# 1_MCUv3.net
KiCad netlist of a schematic drawn in Altium Designer
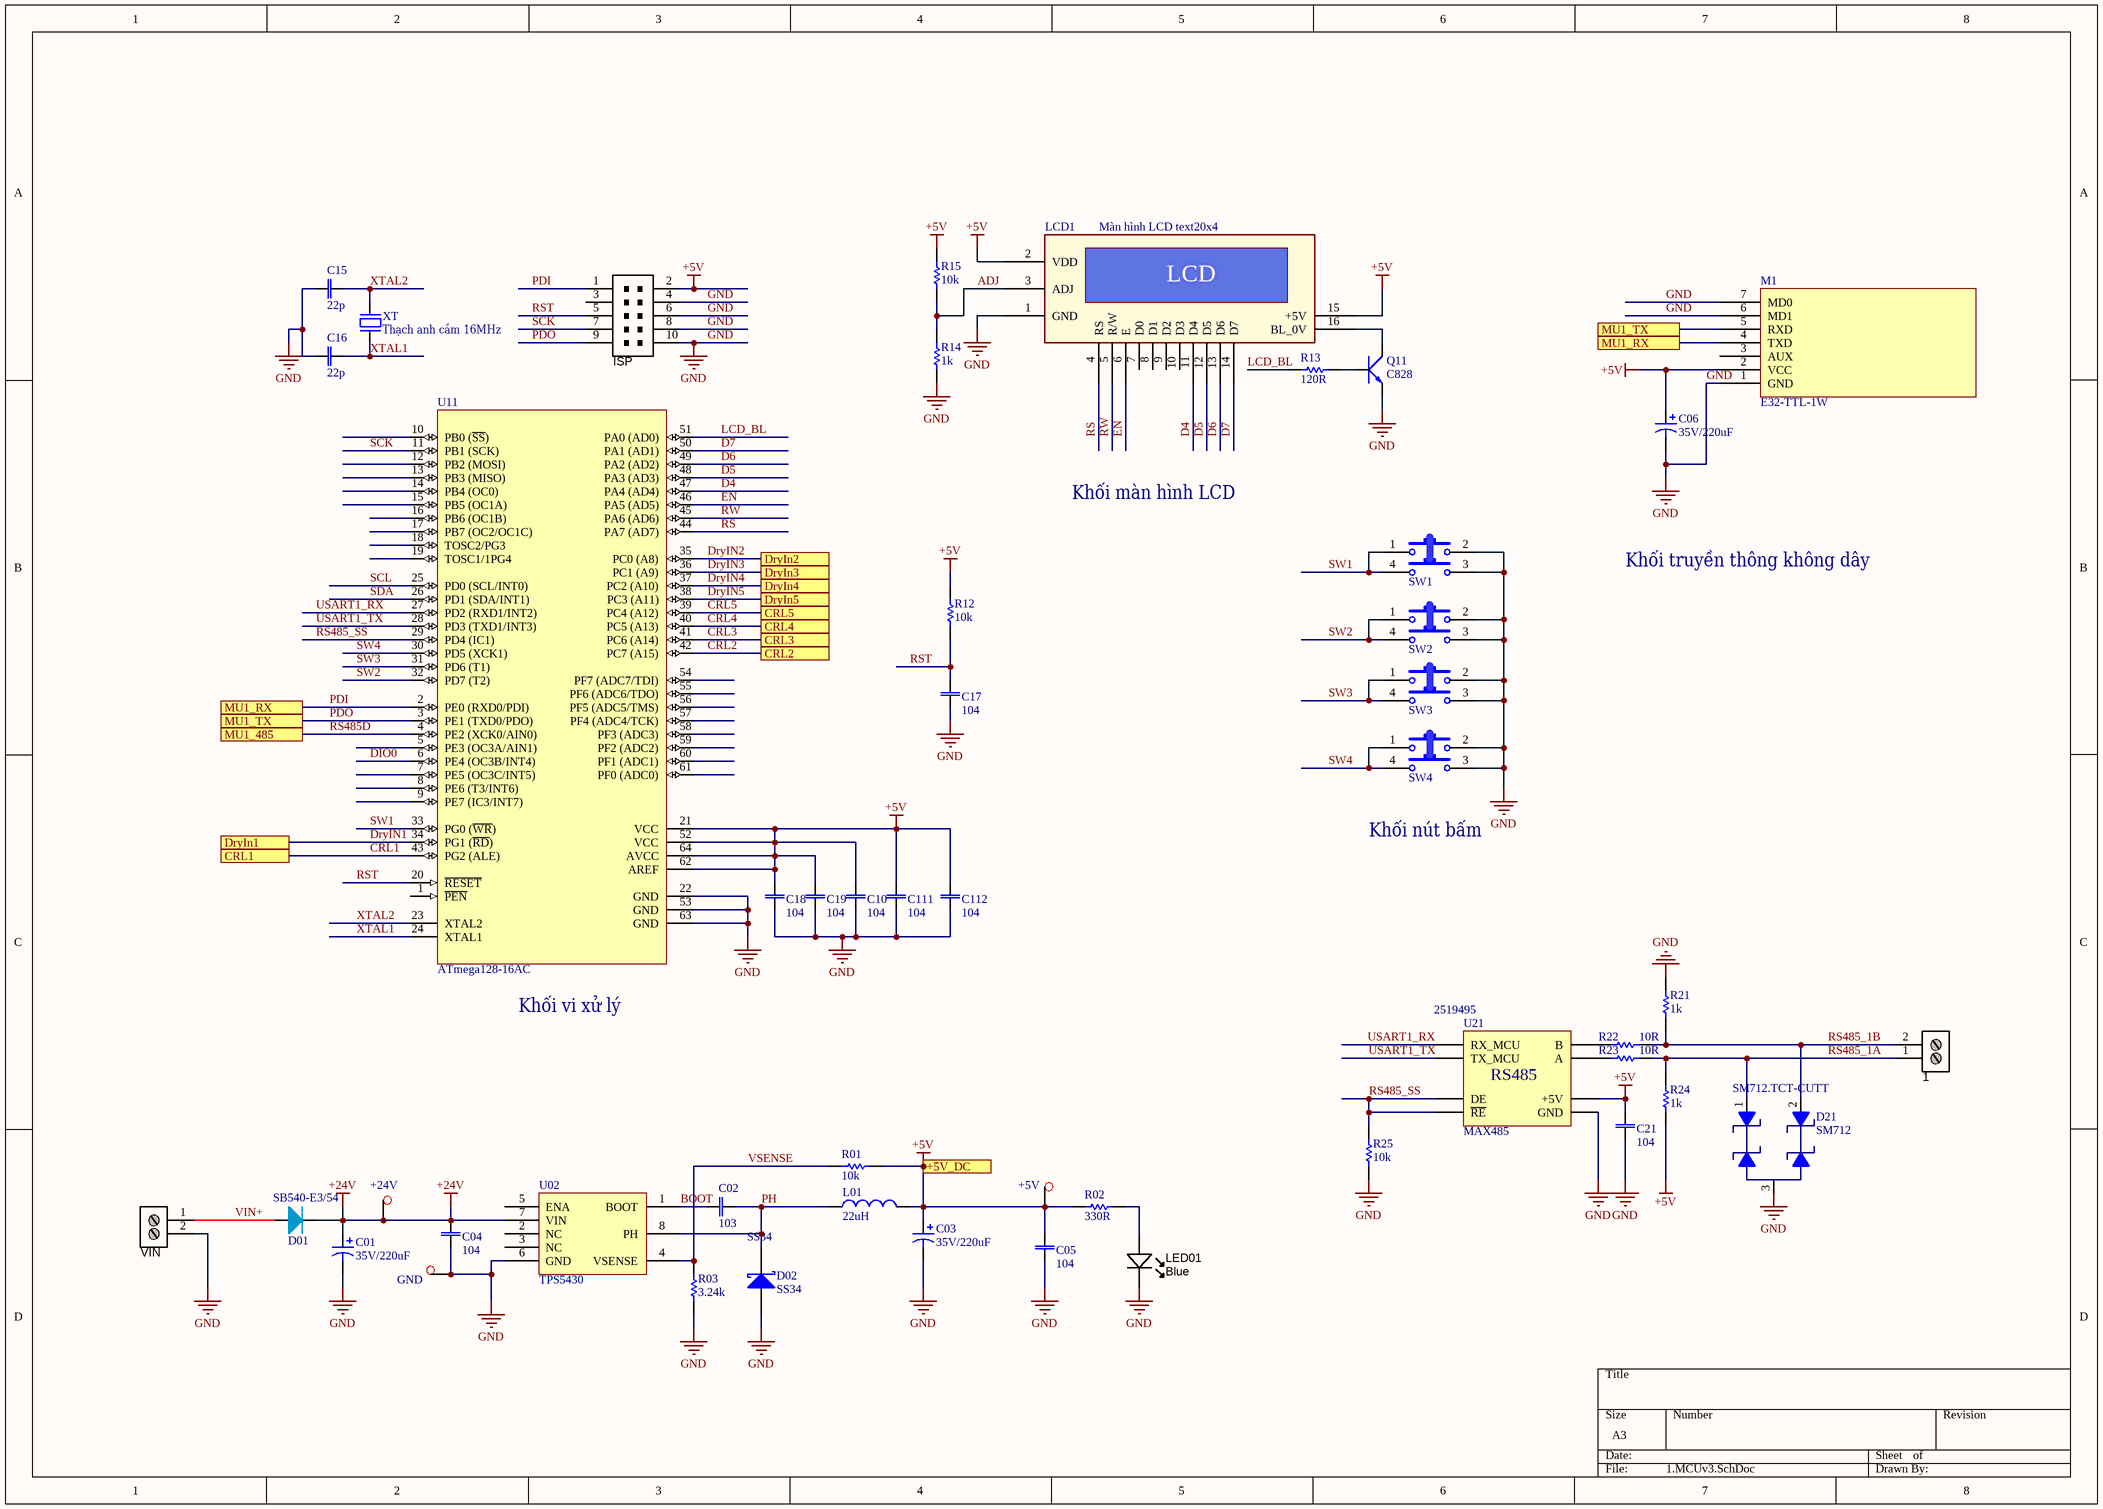
[diagram p0: 1.MCUv3.SchDoc]

(export (version "E")
  (design (tool "Eeschema 10.0.6"))
  (components
    (comp (ref "+5V") (value "TP") (footprint "swatpcblib:TP2") (libsource (lib "swatpcblib") (part "TP")))
    (comp (ref "+24V") (value "TP") (footprint "swatpcblib:TP2") (libsource (lib "swatpcblib") (part "TP")))
    (comp (ref "1")
      (value "Giắc xanh 5.08mm")
      (footprint "2P_PCB1")
      (description "Terminal Block Screw Type THT 2-Position 3.81mm pitch")
      (libsource (lib "PBL - Connectors") (part "2P_ScrewTerm_90S_3.81MM"))
    )
    (comp (ref "C01")
      (value "35V/220uF")
      (footprint "CAPE3.5-5.0MM_Rad_10x14mm")
      (fields (field (name "Comment") "Tụ nhôm cắm35V/220uF"))
      (libsource (lib "Tuan") (part "Cap"))
    )
    (comp (ref "C02")
      (value "103")
      (footprint "swatpcblib:CAP 0805")
      (description "Capacitor non polarized")
      (fields (field (name "Comment") "Tụ điện dán 0805103"))
      (libsource (lib "swatpcblib") (part "CAP NP"))
    )
    (comp (ref "C03")
      (value "35V/220uF")
      (footprint "CAPE3.5-5.0MM_Rad_10x14mm")
      (fields (field (name "Comment") "Tụ nhôm cắm35V/220uF"))
      (libsource (lib "Tuan") (part "Cap"))
    )
    (comp (ref "C04")
      (value "104")
      (footprint "swatpcblib:CAP 0805")
      (description "Capacitor non polarized")
      (fields (field (name "Comment") "Tụ điện dán 0805104"))
      (libsource (lib "swatpcblib") (part "CAP NP"))
    )
    (comp (ref "C05")
      (value "104")
      (footprint "swatpcblib:CAP 0805")
      (description "Capacitor non polarized")
      (fields (field (name "Comment") "Tụ điện dán 0805104"))
      (libsource (lib "swatpcblib") (part "CAP NP"))
    )
    (comp (ref "C06")
      (value "35V/220uF")
      (footprint "CAPE3.5-5.0MM_Rad_10x14mm")
      (fields (field (name "Comment") "Tụ nhôm cắm35V/220uF"))
      (libsource (lib "Tuan") (part "Cap"))
    )
    (comp (ref "C10")
      (value "104")
      (footprint "swatpcblib:CAP 0805")
      (description "Capacitor non polarized")
      (fields (field (name "Comment") "Tụ điện dán 0805104"))
      (libsource (lib "Tuan") (part "CAP NP"))
    )
    (comp (ref "C15")
      (value "22p")
      (footprint "swatpcblib:CAP 0805")
      (description "Capacitor non polarized")
      (fields (field (name "Comment") "Tụ điện dán 080522p"))
      (libsource (lib "Tuan") (part "CAP NP"))
    )
    (comp (ref "C16")
      (value "22p")
      (footprint "swatpcblib:CAP 0805")
      (description "Capacitor non polarized")
      (fields (field (name "Comment") "Tụ điện dán 080522p"))
      (libsource (lib "Tuan") (part "CAP NP"))
    )
    (comp (ref "C17")
      (value "104")
      (footprint "swatpcblib:CAP 0805")
      (description "Capacitor non polarized")
      (fields (field (name "Comment") "Tụ điện dán 0805104"))
      (libsource (lib "Tuan") (part "CAP NP"))
    )
    (comp (ref "C18")
      (value "104")
      (footprint "swatpcblib:CAP 0805")
      (description "Capacitor non polarized")
      (fields (field (name "Comment") "Tụ điện dán 0805104"))
      (libsource (lib "Tuan") (part "CAP NP"))
    )
    (comp (ref "C19")
      (value "104")
      (footprint "swatpcblib:CAP 0805")
      (description "Capacitor non polarized")
      (fields (field (name "Comment") "Tụ điện dán 0805104"))
      (libsource (lib "Tuan") (part "CAP NP"))
    )
    (comp (ref "C21")
      (value "104")
      (footprint "swatpcblib:CAP 0805")
      (description "Capacitor non polarized")
      (fields (field (name "Comment") "Tụ điện dán 0805104"))
      (libsource (lib "Tuan") (part "CAP NP"))
    )
    (comp (ref "C111")
      (value "104")
      (footprint "swatpcblib:CAP 0805")
      (description "Capacitor non polarized")
      (fields (field (name "Comment") "Tụ điện dán 0805104"))
      (libsource (lib "Tuan") (part "CAP NP"))
    )
    (comp (ref "C112")
      (value "104")
      (footprint "swatpcblib:CAP 0805")
      (description "Capacitor non polarized")
      (fields (field (name "Comment") "Tụ điện dán 0805104"))
      (libsource (lib "Tuan") (part "CAP NP"))
    )
    (comp (ref "D01")
      (value "Đi ốt dánchân DO-214AB")
      (footprint "DO-214AA")
      (fields
        (field (name "SUPPLIER PART NUMBER 1") "SB540-E3/54")
        (field (name "MANUFACTURER") "Vishay")
        (field (name "MANUFACTURER PART NUMBER") "SB540-E3/54")
        (field (name "VOLTAGE") "40V")
      )
      (libsource (lib "Tuan") (part "Diode"))
    )
    (comp (ref "D02")
      (value "SS34")
      (footprint "SMD diode")
      (fields
        (field (name "SUPPLIER PART NUMBER 1") "SS34")
        (field (name "MANUFACTURER") "ON Semiconductor / Fairchild")
        (field (name "VOLTAGE") "40V")
      )
      (libsource (lib "Tuan") (part "Diode Schottky"))
    )
    (comp (ref "D21")
      (value "SM712")
      (footprint "SOT23 TOP")
      (fields
        (field (name "SUPPLIER PART NUMBER 1") "SM712.TCT-CUTT")
        (field (name "MANUFACTURER") "Semtech")
        (field (name "MANUFACTURER PART NUMBER") "SM712.TCT")
      )
      (libsource (lib "swatpcblib") (part "Diode SM712"))
    )
    (comp (ref "GND") (value "TP") (footprint "swatpcblib:TP2") (libsource (lib "swatpcblib") (part "TP")))
    (comp (ref "ISP")
      (value "Giắc đôi 5x2 chân 2.54mm")
      (footprint "10P_PCB_HEADER_BRD_MNT")
      (description "Header THD 10 POS Double-row 2.54mm pitch")
      (libsource (lib "PBL - Connectors") (part "CONN_HEADER_2x5P_0.100in_Male"))
    )
    (comp (ref "L01")
      (value "22uH")
      (footprint "Inductor 12x12x6")
      (fields (field (name "Comment") "Cuộn cảm dán22uH"))
      (libsource (lib "swatpcblib") (part "Inductor"))
    )
    (comp (ref "LCD1")
      (value "Màn hình LCD text20x4")
      (footprint "LCD 20x4")
      (description "Text LCD")
      (libsource (lib "Tuan") (part "LCD 16x2"))
    )
    (comp (ref "LED01")
      (value "Blue")
      (footprint "LED-0805-K")
      (description "LED 0805 SMD Blue 100mcd 470nm")
      (fields (field (name "COLOR") "Blue"))
      (libsource (lib "PBL - Light Sources") (part "LED_SMD_Blue_0805_100mcd"))
    )
    (comp (ref "M1")
      (value "E32-TTL-1W")
      (footprint "RF_AS32")
      (description "AS32-TTL-1W")
      (fields (field (name "Comment") "Module thu phát không dây RFE32-TTL-1W"))
      (libsource (lib "DnsSchLib") (part "AS32-TTL-1W"))
    )
    (comp (ref "Q11")
      (value "C828")
      (footprint "SOT23 TOP")
      (description "Transistor C828 C1815....")
      (libsource (lib "Tuan") (part "NPN"))
    )
    (comp (ref "R01")
      (value "10k")
      (footprint "swatpcblib:RES 0805")
      (description "Resistor")
      (fields (field (name "Comment") "Điện trở dán 080510k"))
      (libsource (lib "swatpcblib") (part "Res"))
    )
    (comp (ref "R02")
      (value "330R")
      (footprint "swatpcblib:RES 0805")
      (description "Resistor")
      (fields (field (name "Comment") "Điện trở dán 0805330R"))
      (libsource (lib "swatpcblib") (part "Res"))
    )
    (comp (ref "R03")
      (value "3.24k")
      (footprint "swatpcblib:RES 0805")
      (description "Resistor")
      (fields (field (name "Comment") "Điện trở dán 08053.24k"))
      (libsource (lib "swatpcblib") (part "Res"))
    )
    (comp (ref "R12")
      (value "10k")
      (footprint "swatpcblib:RES 0805")
      (description "Resistor")
      (fields (field (name "Comment") "Điện trở dán 080510k"))
      (libsource (lib "Tuan") (part "Res"))
    )
    (comp (ref "R13")
      (value "120R")
      (footprint "swatpcblib:RES 0805")
      (description "Resistor")
      (fields (field (name "Comment") "Điện trở dán 0805120R"))
      (libsource (lib "Tuan") (part "Res"))
    )
    (comp (ref "R14")
      (value "1k")
      (footprint "swatpcblib:RES 0805")
      (description "Resistor")
      (fields (field (name "Comment") "Điện trở dán 08051k"))
      (libsource (lib "Tuan") (part "Res"))
    )
    (comp (ref "R15")
      (value "10k")
      (footprint "swatpcblib:RES 0805")
      (description "Resistor")
      (fields (field (name "Comment") "Điện trở dán 080510k"))
      (libsource (lib "Tuan") (part "Res"))
    )
    (comp (ref "R21")
      (value "1k")
      (footprint "swatpcblib:RES 0805")
      (description "Resistor")
      (fields (field (name "Comment") "Điện trở dán 08051k"))
      (libsource (lib "Tuan") (part "Res"))
    )
    (comp (ref "R22")
      (value "10R")
      (footprint "swatpcblib:RES 0805")
      (description "Resistor")
      (fields (field (name "Comment") "Điện trở dán 080510R"))
      (libsource (lib "Tuan") (part "Res"))
    )
    (comp (ref "R23")
      (value "10R")
      (footprint "swatpcblib:RES 0805")
      (description "Resistor")
      (fields (field (name "Comment") "Điện trở dán 080510R"))
      (libsource (lib "Tuan") (part "Res"))
    )
    (comp (ref "R24")
      (value "1k")
      (footprint "swatpcblib:RES 0805")
      (description "Resistor")
      (fields (field (name "Comment") "Điện trở dán 08051k"))
      (libsource (lib "Tuan") (part "Res"))
    )
    (comp (ref "R25")
      (value "10k")
      (footprint "swatpcblib:RES 0805")
      (description "Resistor")
      (fields (field (name "Comment") "Điện trở dán 080510k"))
      (libsource (lib "Tuan") (part "Res"))
    )
    (comp (ref "SW1")
      (value "Nút bấm 4 chân cắm12x12x6mm")
      (footprint "hayqua:SW 12x12x4")
      (libsource (lib "Tuan") (part "SW-4P-Small"))
    )
    (comp (ref "SW2")
      (value "Nút bấm 4 chân cắm12x12x6mm")
      (footprint "hayqua:SW 12x12x4")
      (libsource (lib "Tuan") (part "SW-4P-Small"))
    )
    (comp (ref "SW3")
      (value "Nút bấm 4 chân cắm12x12x6mm")
      (footprint "hayqua:SW 12x12x4")
      (libsource (lib "Tuan") (part "SW-4P-Small"))
    )
    (comp (ref "SW4")
      (value "Nút bấm 4 chân cắm12x12x6mm")
      (footprint "hayqua:SW 12x12x4")
      (libsource (lib "Tuan") (part "SW-4P-Small"))
    )
    (comp (ref "U02") (value "TPS5430") (footprint "SOIC 8") (libsource (lib "Tuan") (part "TPS5430")))
    (comp (ref "U11")
      (value "ATmega128-16AC")
      (footprint "64A_N")
      (description "8-Bit AVR Microcontroller with 128K Bytes of In-System Programmable Flash Memory")
      (fields (field (name "PUBLISHER") "Altium Limited"))
      (libsource (lib "Atmel Microcontroller 8-Bit AVR") (part "ATmega128-16AC"))
    )
    (comp (ref "U21")
      (value "MAX4858 chân cắm")
      (footprint "SOIC 8")
      (description "RS485")
      (fields
        (field (name "VL2") "MAX485")
        (field (name "SUPPLIER PART NUMBER 1") "2519495")
        (field (name "MANUFACTURER") "Maxim")
        (field (name "MANUFACTURER PART NUMBER") "MAX485CSA+")
      )
      (libsource (lib "swatpcblib") (part "485"))
    )
    (comp (ref "VIN")
      (value "Giắc xanh 5.08mm")
      (footprint "2P_PCB1")
      (description "Terminal Block Screw Type THT 2-Position 3.81mm pitch")
      (libsource (lib "") (part "2P_ScrewTerm_90S_3.81MM_1"))
    )
    (comp (ref "XT")
      (value "Thạch anh cắm 16MHz")
      (footprint "XT2")
      (libsource (lib "Tuan") (part "Crystal"))
    )
  )
  (nets
    (net (code "1") (name "+5V") (class "Default")
      (node (ref "+5V") (pin "1") (pinfunction "1_1") (pintype "passive"))
      (node (ref "C03") (pin "1") (pinfunction "1_1") (pintype "passive"))
      (node (ref "C05") (pin "2") (pinfunction "2_2") (pintype "passive"))
      (node (ref "C06") (pin "1") (pinfunction "1_1") (pintype "passive"))
      (node (ref "C10") (pin "2") (pinfunction "2_2") (pintype "passive"))
      (node (ref "C111") (pin "2") (pinfunction "2_2") (pintype "passive"))
      (node (ref "C112") (pin "2") (pinfunction "2_2") (pintype "passive"))
      (node (ref "C18") (pin "2") (pinfunction "2_2") (pintype "passive"))
      (node (ref "C19") (pin "2") (pinfunction "2_2") (pintype "passive"))
      (node (ref "C21") (pin "1") (pinfunction "1_1") (pintype "passive"))
      (node (ref "ISP") (pin "2") (pinfunction "2_2") (pintype "passive"))
      (node (ref "L01") (pin "2") (pinfunction "2_2") (pintype "passive"))
      (node (ref "LCD1") (pin "15") (pinfunction "+5V_15") (pintype "passive"))
      (node (ref "LCD1") (pin "2") (pinfunction "VDD_2") (pintype "passive"))
      (node (ref "M1") (pin "2") (pinfunction "VCC_2") (pintype "passive"))
      (node (ref "R01") (pin "1") (pinfunction "1_1") (pintype "passive"))
      (node (ref "R02") (pin "2") (pinfunction "2_2") (pintype "passive"))
      (node (ref "R12") (pin "2") (pinfunction "2_2") (pintype "passive"))
      (node (ref "R15") (pin "2") (pinfunction "2_2") (pintype "passive"))
      (node (ref "R24") (pin "1") (pinfunction "1_1") (pintype "passive"))
      (node (ref "U11") (pin "21") (pinfunction "VCC_21") (pintype "power_in"))
      (node (ref "U11") (pin "52") (pinfunction "VCC_52") (pintype "power_in"))
      (node (ref "U11") (pin "62") (pinfunction "AREF_62") (pintype "passive"))
      (node (ref "U11") (pin "64") (pinfunction "AVCC_64") (pintype "power_in"))
      (node (ref "U21") (pin "8") (pinfunction "+5V_8") (pintype "passive"))
    )
    (net (code "2") (name "+24V") (class "Default")
      (node (ref "+24V") (pin "1") (pinfunction "1_1") (pintype "passive"))
      (node (ref "C01") (pin "1") (pinfunction "1_1") (pintype "passive"))
      (node (ref "C04") (pin "2") (pinfunction "2_2") (pintype "passive"))
      (node (ref "D01") (pin "2") (pinfunction "K_2") (pintype "passive"))
      (node (ref "U02") (pin "7") (pinfunction "VIN_7") (pintype "power_in"))
    )
    (net (code "3") (name "/ADJ") (class "Default")
      (node (ref "LCD1") (pin "3") (pinfunction "ADJ_3") (pintype "passive"))
      (node (ref "R14") (pin "2") (pinfunction "2_2") (pintype "passive"))
      (node (ref "R15") (pin "1") (pinfunction "1_1") (pintype "passive"))
    )
    (net (code "4") (name "/BOOT") (class "Default")
      (node (ref "C02") (pin "1") (pinfunction "1_1") (pintype "passive"))
      (node (ref "U02") (pin "1") (pinfunction "BOOT_1") (pintype "power_in"))
    )
    (net (code "5") (name "/CRL1") (class "Default")
      (node (ref "U11") (pin "43") (pinfunction "PG2_(ALE)_43") (pintype "bidirectional"))
    )
    (net (code "6") (name "/CRL2") (class "Default")
      (node (ref "U11") (pin "42") (pinfunction "PC7_(A15)_42") (pintype "bidirectional"))
    )
    (net (code "7") (name "/CRL3") (class "Default")
      (node (ref "U11") (pin "41") (pinfunction "PC6_(A14)_41") (pintype "bidirectional"))
    )
    (net (code "8") (name "/CRL4") (class "Default")
      (node (ref "U11") (pin "40") (pinfunction "PC5_(A13)_40") (pintype "bidirectional"))
    )
    (net (code "9") (name "/CRL5") (class "Default")
      (node (ref "U11") (pin "39") (pinfunction "PC4_(A12)_39") (pintype "bidirectional"))
    )
    (net (code "10") (name "/D4") (class "Default")
      (node (ref "LCD1") (pin "11") (pinfunction "D4_11") (pintype "passive"))
      (node (ref "U11") (pin "47") (pinfunction "PA4_(AD4)_47") (pintype "bidirectional"))
    )
    (net (code "11") (name "/D5") (class "Default")
      (node (ref "LCD1") (pin "12") (pinfunction "D5_12") (pintype "passive"))
      (node (ref "U11") (pin "48") (pinfunction "PA3_(AD3)_48") (pintype "bidirectional"))
    )
    (net (code "12") (name "/D6") (class "Default")
      (node (ref "LCD1") (pin "13") (pinfunction "D6_13") (pintype "passive"))
      (node (ref "U11") (pin "49") (pinfunction "PA2_(AD2)_49") (pintype "bidirectional"))
    )
    (net (code "13") (name "/D7") (class "Default")
      (node (ref "LCD1") (pin "14") (pinfunction "D7_14") (pintype "passive"))
      (node (ref "U11") (pin "50") (pinfunction "PA1_(AD1)_50") (pintype "bidirectional"))
    )
    (net (code "14") (name "/DIO0") (class "Default")
      (node (ref "U11") (pin "6") (pinfunction "PE4_(OC3B/INT4)_6") (pintype "bidirectional"))
    )
    (net (code "15") (name "/DryIN1") (class "Default")
      (node (ref "U11") (pin "34") (pinfunction "PG1_(~{RD})_34") (pintype "bidirectional"))
    )
    (net (code "16") (name "/DryIN2") (class "Default")
      (node (ref "U11") (pin "35") (pinfunction "PC0_(A8)_35") (pintype "bidirectional"))
    )
    (net (code "17") (name "/DryIN3") (class "Default")
      (node (ref "U11") (pin "36") (pinfunction "PC1_(A9)_36") (pintype "bidirectional"))
    )
    (net (code "18") (name "/DryIN4") (class "Default")
      (node (ref "U11") (pin "37") (pinfunction "PC2_(A10)_37") (pintype "bidirectional"))
    )
    (net (code "19") (name "/DryIN5") (class "Default")
      (node (ref "U11") (pin "38") (pinfunction "PC3_(A11)_38") (pintype "bidirectional"))
    )
    (net (code "20") (name "/EN") (class "Default")
      (node (ref "LCD1") (pin "6") (pinfunction "E_6") (pintype "passive"))
      (node (ref "U11") (pin "46") (pinfunction "PA5_(AD5)_46") (pintype "bidirectional"))
    )
    (net (code "21") (name "/LCD_BL") (class "Default")
      (node (ref "R13") (pin "2") (pinfunction "2_2") (pintype "passive"))
      (node (ref "U11") (pin "51") (pinfunction "PA0_(AD0)_51") (pintype "bidirectional"))
    )
    (net (code "22") (name "/PDI") (class "Default")
      (node (ref "ISP") (pin "1") (pinfunction "1_1") (pintype "passive"))
      (node (ref "M1") (pin "4") (pinfunction "TXD_4") (pintype "passive"))
      (node (ref "U11") (pin "2") (pinfunction "PE0_(RXD0/PDI)_2") (pintype "bidirectional"))
    )
    (net (code "23") (name "/PDO") (class "Default")
      (node (ref "ISP") (pin "9") (pinfunction "9_9") (pintype "passive"))
      (node (ref "M1") (pin "5") (pinfunction "RXD_5") (pintype "passive"))
      (node (ref "U11") (pin "3") (pinfunction "PE1_(TXD0/PDO)_3") (pintype "bidirectional"))
    )
    (net (code "24") (name "/PH") (class "Default")
      (node (ref "C02") (pin "2") (pinfunction "2_2") (pintype "passive"))
      (node (ref "D02") (pin "2") (pinfunction "K_2") (pintype "passive"))
      (node (ref "L01") (pin "1") (pinfunction "1_1") (pintype "passive"))
      (node (ref "U02") (pin "8") (pinfunction "PH_8") (pintype "power_in"))
    )
    (net (code "25") (name "/RS") (class "Default")
      (node (ref "LCD1") (pin "4") (pinfunction "RS_4") (pintype "passive"))
      (node (ref "U11") (pin "44") (pinfunction "PA7_(AD7)_44") (pintype "bidirectional"))
    )
    (net (code "26") (name "/RS485D") (class "Default")
      (node (ref "U11") (pin "4") (pinfunction "PE2_(XCK0/AIN0)_4") (pintype "bidirectional"))
    )
    (net (code "27") (name "/RS485_1A") (class "Default")
      (node (ref "1") (pin "1") (pinfunction "1_1") (pintype "passive"))
      (node (ref "D21") (pin "1") (pinfunction "IO1_1") (pintype "passive"))
      (node (ref "R23") (pin "2") (pinfunction "2_2") (pintype "passive"))
      (node (ref "R24") (pin "2") (pinfunction "2_2") (pintype "passive"))
    )
    (net (code "28") (name "/RS485_1B") (class "Default")
      (node (ref "1") (pin "2") (pinfunction "2_2") (pintype "passive"))
      (node (ref "D21") (pin "2") (pinfunction "IO2_2") (pintype "passive"))
      (node (ref "R21") (pin "1") (pinfunction "1_1") (pintype "passive"))
      (node (ref "R22") (pin "2") (pinfunction "2_2") (pintype "passive"))
    )
    (net (code "29") (name "/RS485_SS") (class "Default")
      (node (ref "R25") (pin "2") (pinfunction "2_2") (pintype "passive"))
      (node (ref "U11") (pin "29") (pinfunction "PD4_(IC1)_29") (pintype "bidirectional"))
      (node (ref "U21") (pin "2") (pinfunction "~{RE}_2") (pintype "passive"))
      (node (ref "U21") (pin "3") (pinfunction "DE_3") (pintype "passive"))
    )
    (net (code "30") (name "/RST") (class "Default")
      (node (ref "C17") (pin "2") (pinfunction "2_2") (pintype "passive"))
      (node (ref "ISP") (pin "5") (pinfunction "5_5") (pintype "passive"))
      (node (ref "R12") (pin "1") (pinfunction "1_1") (pintype "passive"))
      (node (ref "U11") (pin "20") (pinfunction "~{RESET}_20") (pintype "input"))
    )
    (net (code "31") (name "/RW") (class "Default")
      (node (ref "LCD1") (pin "5") (pinfunction "R/W_5") (pintype "passive"))
      (node (ref "U11") (pin "45") (pinfunction "PA6_(AD6)_45") (pintype "bidirectional"))
    )
    (net (code "32") (name "/SCK") (class "Default")
      (node (ref "ISP") (pin "7") (pinfunction "7_7") (pintype "passive"))
      (node (ref "U11") (pin "11") (pinfunction "PB1_(SCK)_11") (pintype "bidirectional"))
    )
    (net (code "33") (name "/SCL") (class "Default")
      (node (ref "U11") (pin "25") (pinfunction "PD0_(SCL/INT0)_25") (pintype "bidirectional"))
    )
    (net (code "34") (name "/SDA") (class "Default")
      (node (ref "U11") (pin "26") (pinfunction "PD1_(SDA/INT1)_26") (pintype "bidirectional"))
    )
    (net (code "35") (name "/SW1") (class "Default")
      (node (ref "SW1") (pin "1") (pinfunction "1_1") (pintype "passive"))
      (node (ref "SW1") (pin "4") (pinfunction "4_4") (pintype "passive"))
      (node (ref "U11") (pin "33") (pinfunction "PG0_(~{WR})_33") (pintype "bidirectional"))
    )
    (net (code "36") (name "/SW2") (class "Default")
      (node (ref "SW2") (pin "1") (pinfunction "1_1") (pintype "passive"))
      (node (ref "SW2") (pin "4") (pinfunction "4_4") (pintype "passive"))
      (node (ref "U11") (pin "32") (pinfunction "PD7_(T2)_32") (pintype "bidirectional"))
    )
    (net (code "37") (name "/SW3") (class "Default")
      (node (ref "SW3") (pin "1") (pinfunction "1_1") (pintype "passive"))
      (node (ref "SW3") (pin "4") (pinfunction "4_4") (pintype "passive"))
      (node (ref "U11") (pin "31") (pinfunction "PD6_(T1)_31") (pintype "bidirectional"))
    )
    (net (code "38") (name "/SW4") (class "Default")
      (node (ref "SW4") (pin "1") (pinfunction "1_1") (pintype "passive"))
      (node (ref "SW4") (pin "4") (pinfunction "4_4") (pintype "passive"))
      (node (ref "U11") (pin "30") (pinfunction "PD5_(XCK1)_30") (pintype "bidirectional"))
    )
    (net (code "39") (name "/USART1_RX") (class "Default")
      (node (ref "U11") (pin "27") (pinfunction "PD2_(RXD1/INT2)_27") (pintype "bidirectional"))
      (node (ref "U21") (pin "1") (pinfunction "RX_MCU_1") (pintype "passive"))
    )
    (net (code "40") (name "/USART1_TX") (class "Default")
      (node (ref "U11") (pin "28") (pinfunction "PD3_(TXD1/INT3)_28") (pintype "bidirectional"))
      (node (ref "U21") (pin "4") (pinfunction "TX_MCU_4") (pintype "passive"))
    )
    (net (code "41") (name "/VIN+") (class "Default")
      (node (ref "D01") (pin "1") (pinfunction "A_1") (pintype "passive"))
      (node (ref "VIN") (pin "1") (pinfunction "1_1") (pintype "passive"))
    )
    (net (code "42") (name "/VSENSE") (class "Default")
      (node (ref "R01") (pin "2") (pinfunction "2_2") (pintype "passive"))
      (node (ref "R03") (pin "2") (pinfunction "2_2") (pintype "passive"))
      (node (ref "U02") (pin "4") (pinfunction "VSENSE_4") (pintype "power_in"))
    )
    (net (code "43") (name "/XTAL1") (class "Default")
      (node (ref "C16") (pin "1") (pinfunction "1_1") (pintype "passive"))
      (node (ref "U11") (pin "24") (pinfunction "XTAL1_24") (pintype "passive"))
      (node (ref "XT") (pin "1") (pinfunction "1_1") (pintype "passive"))
    )
    (net (code "44") (name "/XTAL2") (class "Default")
      (node (ref "C15") (pin "1") (pinfunction "1_1") (pintype "passive"))
      (node (ref "U11") (pin "23") (pinfunction "XTAL2_23") (pintype "passive"))
      (node (ref "XT") (pin "2") (pinfunction "2_2") (pintype "passive"))
    )
    (net (code "45") (name "GND") (class "Default")
      (node (ref "C01") (pin "2") (pinfunction "2_2") (pintype "passive"))
      (node (ref "C03") (pin "2") (pinfunction "2_2") (pintype "passive"))
      (node (ref "C04") (pin "1") (pinfunction "1_1") (pintype "passive"))
      (node (ref "C05") (pin "1") (pinfunction "1_1") (pintype "passive"))
      (node (ref "C06") (pin "2") (pinfunction "2_2") (pintype "passive"))
      (node (ref "C10") (pin "1") (pinfunction "1_1") (pintype "passive"))
      (node (ref "C111") (pin "1") (pinfunction "1_1") (pintype "passive"))
      (node (ref "C112") (pin "1") (pinfunction "1_1") (pintype "passive"))
      (node (ref "C15") (pin "2") (pinfunction "2_2") (pintype "passive"))
      (node (ref "C16") (pin "2") (pinfunction "2_2") (pintype "passive"))
      (node (ref "C17") (pin "1") (pinfunction "1_1") (pintype "passive"))
      (node (ref "C18") (pin "1") (pinfunction "1_1") (pintype "passive"))
      (node (ref "C19") (pin "1") (pinfunction "1_1") (pintype "passive"))
      (node (ref "C21") (pin "2") (pinfunction "2_2") (pintype "passive"))
      (node (ref "D02") (pin "1") (pinfunction "A_1") (pintype "passive"))
      (node (ref "D21") (pin "3") (pinfunction "GND_3") (pintype "passive"))
      (node (ref "GND") (pin "1") (pinfunction "1_1") (pintype "passive"))
      (node (ref "ISP") (pin "10") (pinfunction "10_10") (pintype "passive"))
      (node (ref "ISP") (pin "4") (pinfunction "4_4") (pintype "passive"))
      (node (ref "ISP") (pin "6") (pinfunction "6_6") (pintype "passive"))
      (node (ref "ISP") (pin "8") (pinfunction "8_8") (pintype "passive"))
      (node (ref "LCD1") (pin "1") (pinfunction "GND_1") (pintype "passive"))
      (node (ref "LED01") (pin "K") (pinfunction "K_K") (pintype "passive"))
      (node (ref "M1") (pin "1") (pinfunction "GND_1") (pintype "passive"))
      (node (ref "M1") (pin "6") (pinfunction "MD1_6") (pintype "passive"))
      (node (ref "M1") (pin "7") (pinfunction "MD0_7") (pintype "passive"))
      (node (ref "Q11") (pin "3") (pinfunction "E_3") (pintype "passive"))
      (node (ref "R03") (pin "1") (pinfunction "1_1") (pintype "passive"))
      (node (ref "R14") (pin "1") (pinfunction "1_1") (pintype "passive"))
      (node (ref "R21") (pin "2") (pinfunction "2_2") (pintype "passive"))
      (node (ref "R25") (pin "1") (pinfunction "1_1") (pintype "passive"))
      (node (ref "SW1") (pin "2") (pinfunction "2_2") (pintype "passive"))
      (node (ref "SW1") (pin "3") (pinfunction "3_3") (pintype "passive"))
      (node (ref "SW2") (pin "2") (pinfunction "2_2") (pintype "passive"))
      (node (ref "SW2") (pin "3") (pinfunction "3_3") (pintype "passive"))
      (node (ref "SW3") (pin "2") (pinfunction "2_2") (pintype "passive"))
      (node (ref "SW3") (pin "3") (pinfunction "3_3") (pintype "passive"))
      (node (ref "SW4") (pin "2") (pinfunction "2_2") (pintype "passive"))
      (node (ref "SW4") (pin "3") (pinfunction "3_3") (pintype "passive"))
      (node (ref "U02") (pin "6") (pinfunction "GND_6") (pintype "power_in"))
      (node (ref "U11") (pin "22") (pinfunction "GND_22") (pintype "power_in"))
      (node (ref "U11") (pin "53") (pinfunction "GND_53") (pintype "power_in"))
      (node (ref "U11") (pin "63") (pinfunction "GND_63") (pintype "power_in"))
      (node (ref "U21") (pin "5") (pinfunction "GND_5") (pintype "passive"))
      (node (ref "VIN") (pin "2") (pinfunction "2_2") (pintype "passive"))
    )
    (net (code "46") (name "Net-(LCD1-BL_0V)") (class "Default")
      (node (ref "LCD1") (pin "16") (pinfunction "BL_0V_16") (pintype "passive"))
      (node (ref "Q11") (pin "2") (pinfunction "C_2") (pintype "passive"))
    )
    (net (code "47") (name "Net-(LED01-PadA)") (class "Default")
      (node (ref "LED01") (pin "A") (pinfunction "A_A") (pintype "passive"))
      (node (ref "R02") (pin "1") (pinfunction "1_1") (pintype "passive"))
    )
    (net (code "48") (name "Net-(Q11-B)") (class "Default")
      (node (ref "Q11") (pin "1") (pinfunction "B_1") (pintype "passive"))
      (node (ref "R13") (pin "1") (pinfunction "1_1") (pintype "passive"))
    )
    (net (code "49") (name "Net-(U21-A)") (class "Default")
      (node (ref "R23") (pin "1") (pinfunction "1_1") (pintype "passive"))
      (node (ref "U21") (pin "6") (pinfunction "A_6") (pintype "passive"))
    )
    (net (code "50") (name "Net-(U21-B)") (class "Default")
      (node (ref "R22") (pin "1") (pinfunction "1_1") (pintype "passive"))
      (node (ref "U21") (pin "7") (pinfunction "B_7") (pintype "passive"))
    )
    (net (code "51") (name "unconnected-(ISP-Pad3)") (class "Default")
      (node (ref "ISP") (pin "3") (pinfunction "3_3") (pintype "passive"))
    )
    (net (code "52") (name "unconnected-(LCD1-D0-Pad7)") (class "Default")
      (node (ref "LCD1") (pin "7") (pinfunction "D0_7") (pintype "passive"))
    )
    (net (code "53") (name "unconnected-(LCD1-D1-Pad8)") (class "Default")
      (node (ref "LCD1") (pin "8") (pinfunction "D1_8") (pintype "passive"))
    )
    (net (code "54") (name "unconnected-(LCD1-D2-Pad9)") (class "Default")
      (node (ref "LCD1") (pin "9") (pinfunction "D2_9") (pintype "passive"))
    )
    (net (code "55") (name "unconnected-(LCD1-D3-Pad10)") (class "Default")
      (node (ref "LCD1") (pin "10") (pinfunction "D3_10") (pintype "passive"))
    )
    (net (code "56") (name "unconnected-(M1-AUX-Pad3)") (class "Default")
      (node (ref "M1") (pin "3") (pinfunction "AUX_3") (pintype "passive"))
    )
    (net (code "57") (name "unconnected-(U02-ENA-Pad5)") (class "Default")
      (node (ref "U02") (pin "5") (pinfunction "ENA_5") (pintype "power_in"))
    )
    (net (code "58") (name "unconnected-(U02-NC-Pad2)") (class "Default")
      (node (ref "U02") (pin "2") (pinfunction "NC_2") (pintype "power_in"))
    )
    (net (code "59") (name "unconnected-(U02-NC-Pad3)") (class "Default")
      (node (ref "U02") (pin "3") (pinfunction "NC_3") (pintype "power_in"))
    )
    (net (code "60") (name "unconnected-(U11-PB0_(~{SS})-Pad10)") (class "Default")
      (node (ref "U11") (pin "10") (pinfunction "PB0_(~{SS})_10") (pintype "bidirectional"))
    )
    (net (code "61") (name "unconnected-(U11-PB2_(MOSI)-Pad12)") (class "Default")
      (node (ref "U11") (pin "12") (pinfunction "PB2_(MOSI)_12") (pintype "bidirectional"))
    )
    (net (code "62") (name "unconnected-(U11-PB3_(MISO)-Pad13)") (class "Default")
      (node (ref "U11") (pin "13") (pinfunction "PB3_(MISO)_13") (pintype "bidirectional"))
    )
    (net (code "63") (name "unconnected-(U11-PB4_(OC0)-Pad14)") (class "Default")
      (node (ref "U11") (pin "14") (pinfunction "PB4_(OC0)_14") (pintype "bidirectional"))
    )
    (net (code "64") (name "unconnected-(U11-PB5_(OC1A)-Pad15)") (class "Default")
      (node (ref "U11") (pin "15") (pinfunction "PB5_(OC1A)_15") (pintype "bidirectional"))
    )
    (net (code "65") (name "unconnected-(U11-PB6_(OC1B)-Pad16)") (class "Default")
      (node (ref "U11") (pin "16") (pinfunction "PB6_(OC1B)_16") (pintype "bidirectional"))
    )
    (net (code "66") (name "unconnected-(U11-PB7_(OC2{slash}OC1C)-Pad17)") (class "Default")
      (node (ref "U11") (pin "17") (pinfunction "PB7_(OC2/OC1C)_17") (pintype "bidirectional"))
    )
    (net (code "67") (name "unconnected-(U11-PE3_(OC3A{slash}AIN1)-Pad5)") (class "Default")
      (node (ref "U11") (pin "5") (pinfunction "PE3_(OC3A/AIN1)_5") (pintype "bidirectional"))
    )
    (net (code "68") (name "unconnected-(U11-PE5_(OC3C{slash}INT5)-Pad7)") (class "Default")
      (node (ref "U11") (pin "7") (pinfunction "PE5_(OC3C/INT5)_7") (pintype "bidirectional"))
    )
    (net (code "69") (name "unconnected-(U11-PE6_(T3{slash}INT6)-Pad8)") (class "Default")
      (node (ref "U11") (pin "8") (pinfunction "PE6_(T3/INT6)_8") (pintype "bidirectional"))
    )
    (net (code "70") (name "unconnected-(U11-PE7_(IC3{slash}INT7)-Pad9)") (class "Default")
      (node (ref "U11") (pin "9") (pinfunction "PE7_(IC3/INT7)_9") (pintype "bidirectional"))
    )
    (net (code "71") (name "unconnected-(U11-PF0_(ADC0)-Pad61)") (class "Default")
      (node (ref "U11") (pin "61") (pinfunction "PF0_(ADC0)_61") (pintype "bidirectional"))
    )
    (net (code "72") (name "unconnected-(U11-PF1_(ADC1)-Pad60)") (class "Default")
      (node (ref "U11") (pin "60") (pinfunction "PF1_(ADC1)_60") (pintype "bidirectional"))
    )
    (net (code "73") (name "unconnected-(U11-PF2_(ADC2)-Pad59)") (class "Default")
      (node (ref "U11") (pin "59") (pinfunction "PF2_(ADC2)_59") (pintype "bidirectional"))
    )
    (net (code "74") (name "unconnected-(U11-PF3_(ADC3)-Pad58)") (class "Default")
      (node (ref "U11") (pin "58") (pinfunction "PF3_(ADC3)_58") (pintype "bidirectional"))
    )
    (net (code "75") (name "unconnected-(U11-PF4_(ADC4{slash}TCK)-Pad57)") (class "Default")
      (node (ref "U11") (pin "57") (pinfunction "PF4_(ADC4/TCK)_57") (pintype "bidirectional"))
    )
    (net (code "76") (name "unconnected-(U11-PF5_(ADC5{slash}TMS)-Pad56)") (class "Default")
      (node (ref "U11") (pin "56") (pinfunction "PF5_(ADC5/TMS)_56") (pintype "bidirectional"))
    )
    (net (code "77") (name "unconnected-(U11-PF6_(ADC6{slash}TDO)-Pad55)") (class "Default")
      (node (ref "U11") (pin "55") (pinfunction "PF6_(ADC6/TDO)_55") (pintype "bidirectional"))
    )
    (net (code "78") (name "unconnected-(U11-PF7_(ADC7{slash}TDI)-Pad54)") (class "Default")
      (node (ref "U11") (pin "54") (pinfunction "PF7_(ADC7/TDI)_54") (pintype "bidirectional"))
    )
    (net (code "79") (name "unconnected-(U11-TOSC1{slash}1PG4-Pad19)") (class "Default")
      (node (ref "U11") (pin "19") (pinfunction "TOSC1/1PG4_19") (pintype "bidirectional"))
    )
    (net (code "80") (name "unconnected-(U11-TOSC2{slash}PG3-Pad18)") (class "Default")
      (node (ref "U11") (pin "18") (pinfunction "TOSC2/PG3_18") (pintype "bidirectional"))
    )
    (net (code "81") (name "unconnected-(U11-~{PEN}-Pad1)") (class "Default")
      (node (ref "U11") (pin "1") (pinfunction "~{PEN}_1") (pintype "input"))
    )
  )
)
